# 04_CONNECTORS.net
KiCad netlist of a schematic drawn in Altium Designer
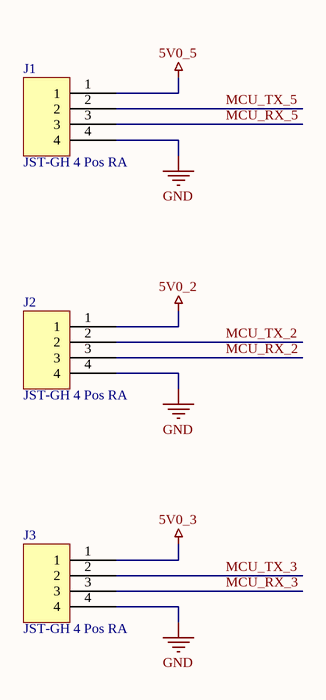
[diagram p0: [04] CONNECTORS.SchDoc]

(export (version "E")
  (design (tool "Eeschema 10.0.6"))
  (components
    (comp (ref "J1")
      (value "JST-GH 4 Pos RA")
      (footprint "SM04B-GHS-TB(LF)(SN)-")
      (description "JST-GH CONN HEADER SMD R/A 4 POS 1.25MM")
      (fields
        (field (name "MANUFACTURER") "JST")
        (field (name "MANUFACTURER PART NUMBER") "SM04B-GHS-TB(LF)(SN)-")
      )
      (libsource (lib "Connectors") (part "SM04B-GHS-TB(LF)(SN)-"))
    )
    (comp (ref "J2")
      (value "JST-GH 4 Pos RA")
      (footprint "SM04B-GHS-TB(LF)(SN)-")
      (description "JST-GH CONN HEADER SMD R/A 4 POS 1.25MM")
      (fields
        (field (name "MANUFACTURER") "JST")
        (field (name "MANUFACTURER PART NUMBER") "SM04B-GHS-TB(LF)(SN)-")
      )
      (libsource (lib "Connectors") (part "SM04B-GHS-TB(LF)(SN)-"))
    )
    (comp (ref "J3")
      (value "JST-GH 4 Pos RA")
      (footprint "SM04B-GHS-TB(LF)(SN)-")
      (description "JST-GH CONN HEADER SMD R/A 4 POS 1.25MM")
      (fields
        (field (name "MANUFACTURER") "JST")
        (field (name "MANUFACTURER PART NUMBER") "SM04B-GHS-TB(LF)(SN)-")
      )
      (libsource (lib "Connectors") (part "SM04B-GHS-TB(LF)(SN)-"))
    )
  )
  (nets
    (net (code "1") (name "/MCU_RX_2") (class "Default")
      (node (ref "J2") (pin "3") (pinfunction "3_3") (pintype "passive"))
    )
    (net (code "2") (name "/MCU_RX_3") (class "Default")
      (node (ref "J3") (pin "3") (pinfunction "3_3") (pintype "passive"))
    )
    (net (code "3") (name "/MCU_RX_5") (class "Default")
      (node (ref "J1") (pin "3") (pinfunction "3_3") (pintype "passive"))
    )
    (net (code "4") (name "/MCU_TX_2") (class "Default")
      (node (ref "J2") (pin "2") (pinfunction "2_2") (pintype "passive"))
    )
    (net (code "5") (name "/MCU_TX_3") (class "Default")
      (node (ref "J3") (pin "2") (pinfunction "2_2") (pintype "passive"))
    )
    (net (code "6") (name "/MCU_TX_5") (class "Default")
      (node (ref "J1") (pin "2") (pinfunction "2_2") (pintype "passive"))
    )
    (net (code "7") (name "5V0_2") (class "Default")
      (node (ref "J2") (pin "1") (pinfunction "1_1") (pintype "passive"))
    )
    (net (code "8") (name "5V0_3") (class "Default")
      (node (ref "J3") (pin "1") (pinfunction "1_1") (pintype "passive"))
    )
    (net (code "9") (name "5V0_5") (class "Default")
      (node (ref "J1") (pin "1") (pinfunction "1_1") (pintype "passive"))
    )
    (net (code "10") (name "GND") (class "Default")
      (node (ref "J1") (pin "4") (pinfunction "4_4") (pintype "passive"))
      (node (ref "J2") (pin "4") (pinfunction "4_4") (pintype "passive"))
      (node (ref "J3") (pin "4") (pinfunction "4_4") (pintype "passive"))
    )
  )
)
